# max1811smd.net
KiCad netlist of a schematic drawn in EAGLE
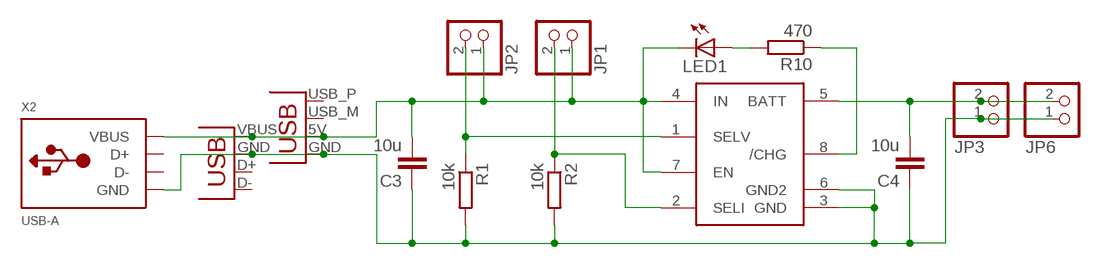
[diagram p0: schematic, sheet 1]

(export (version "E")
  (design (tool "Eeschema 10.0.6"))
  (components
    (comp (ref "C3")
      (value "10u")
      (footprint "eagle-import:C0805K")
      (libsource (lib "eagle-import") (part "C-EUC0805K"))
    )
    (comp (ref "C4")
      (value "10u")
      (footprint "eagle-import:C0805K")
      (libsource (lib "eagle-import") (part "C-EUC0805K"))
    )
    (comp (ref "CN1")
      (value "USBPCB")
      (footprint "eagle-import:USB-A-PCB")
      (libsource (lib "eagle-import") (part "USBPCB"))
    )
    (comp (ref "JP1")
      (value "PINHD-1X2")
      (footprint "eagle-import:1X02")
      (libsource (lib "eagle-import") (part "PINHD-1X2"))
    )
    (comp (ref "JP2")
      (value "PINHD-1X2")
      (footprint "eagle-import:1X02")
      (libsource (lib "eagle-import") (part "PINHD-1X2"))
    )
    (comp (ref "JP3")
      (value "PINHD-1X2")
      (footprint "eagle-import:1X02")
      (libsource (lib "eagle-import") (part "PINHD-1X2"))
    )
    (comp (ref "JP6")
      (value "PINHD-1X2")
      (footprint "eagle-import:1X02")
      (libsource (lib "eagle-import") (part "PINHD-1X2"))
    )
    (comp (ref "LED1")
      (value "LEDCHIPLED_0805")
      (footprint "eagle-import:CHIPLED_0805")
      (libsource (lib "eagle-import") (part "LEDCHIPLED_0805"))
    )
    (comp (ref "R1")
      (value "10k")
      (footprint "eagle-import:M0805")
      (libsource (lib "eagle-import") (part "R-EU_M0805"))
    )
    (comp (ref "R2")
      (value "10k")
      (footprint "eagle-import:M0805")
      (libsource (lib "eagle-import") (part "R-EU_M0805"))
    )
    (comp (ref "R10")
      (value "470")
      (footprint "eagle-import:M0805")
      (libsource (lib "eagle-import") (part "R-EU_M0805"))
    )
    (comp (ref "U$1")
      (value "MAX1811SO8")
      (footprint "eagle-import:SO08")
      (libsource (lib "eagle-import") (part "MAX1811SO8"))
    )
    (comp (ref "X1")
      (value "USB-A-H")
      (footprint "eagle-import:USB-A-H")
      (libsource (lib "eagle-import") (part "USB-A-H"))
    )
    (comp (ref "X2")
      (value "USB-A")
      (footprint "eagle-import:MOLEX_480371000")
      (libsource (lib "eagle-import") (part "USB-A"))
    )
  )
  (nets
    (net (code "1") (name "Net-(CN1-VBUS)") (class "Default")
      (node (ref "C3") (pin "2") (pinfunction "2_2") (pintype "passive"))
      (node (ref "CN1") (pin "5V") (pinfunction "VBUS_5V") (pintype "bidirectional"))
      (node (ref "JP1") (pin "1") (pinfunction "1_1") (pintype "passive"))
      (node (ref "JP2") (pin "1") (pinfunction "1_1") (pintype "passive"))
      (node (ref "LED1") (pin "C") (pinfunction "C_C") (pintype "passive"))
      (node (ref "U$1") (pin "4") (pinfunction "IN_4") (pintype "bidirectional"))
      (node (ref "U$1") (pin "7") (pinfunction "EN_7") (pintype "bidirectional"))
      (node (ref "X1") (pin "VBUS") (pinfunction "GND_VBUS") (pintype "bidirectional"))
      (node (ref "X2") (pin "1") (pinfunction "VBUS_1") (pintype "power_in"))
    )
    (net (code "2") (name "Net-(LED1-PadA)") (class "Default")
      (node (ref "LED1") (pin "A") (pinfunction "A_A") (pintype "passive"))
      (node (ref "R10") (pin "2") (pinfunction "2_2") (pintype "passive"))
    )
    (net (code "3") (name "Net-(U$1-BATT)") (class "Default")
      (node (ref "C4") (pin "2") (pinfunction "2_2") (pintype "passive"))
      (node (ref "JP3") (pin "2") (pinfunction "2_2") (pintype "passive"))
      (node (ref "JP6") (pin "2") (pinfunction "2_2") (pintype "passive"))
      (node (ref "U$1") (pin "5") (pinfunction "BATT_5") (pintype "bidirectional"))
    )
    (net (code "4") (name "Net-(U$1-GND)") (class "Default")
      (node (ref "C3") (pin "1") (pinfunction "1_1") (pintype "passive"))
      (node (ref "C4") (pin "1") (pinfunction "1_1") (pintype "passive"))
      (node (ref "CN1") (pin "GND") (pinfunction "GND_GND") (pintype "bidirectional"))
      (node (ref "JP3") (pin "1") (pinfunction "1_1") (pintype "passive"))
      (node (ref "JP6") (pin "1") (pinfunction "1_1") (pintype "passive"))
      (node (ref "R1") (pin "2") (pinfunction "2_2") (pintype "passive"))
      (node (ref "R2") (pin "2") (pinfunction "2_2") (pintype "passive"))
      (node (ref "U$1") (pin "3") (pinfunction "GND_3") (pintype "bidirectional"))
      (node (ref "U$1") (pin "6") (pinfunction "GND2_6") (pintype "bidirectional"))
      (node (ref "X1") (pin "GND") (pinfunction "VBUS_GND") (pintype "bidirectional"))
      (node (ref "X2") (pin "4") (pinfunction "GND_4") (pintype "power_in"))
    )
    (net (code "5") (name "Net-(U$1-SELI)") (class "Default")
      (node (ref "JP1") (pin "2") (pinfunction "2_2") (pintype "passive"))
      (node (ref "R2") (pin "1") (pinfunction "1_1") (pintype "passive"))
      (node (ref "U$1") (pin "2") (pinfunction "SELI_2") (pintype "bidirectional"))
    )
    (net (code "6") (name "Net-(U$1-SELV)") (class "Default")
      (node (ref "JP2") (pin "2") (pinfunction "2_2") (pintype "passive"))
      (node (ref "R1") (pin "1") (pinfunction "1_1") (pintype "passive"))
      (node (ref "U$1") (pin "1") (pinfunction "SELV_1") (pintype "bidirectional"))
    )
    (net (code "7") (name "Net-(U$1-{slash}CHG)") (class "Default")
      (node (ref "R10") (pin "1") (pinfunction "1_1") (pintype "passive"))
      (node (ref "U$1") (pin "8") (pinfunction "/CHG_8") (pintype "bidirectional"))
    )
    (net (code "8") (name "unconnected-(CN1-D+-PadUSB_P)") (class "Default")
      (node (ref "CN1") (pin "USB_P") (pinfunction "D+_USB_P") (pintype "bidirectional"))
    )
    (net (code "9") (name "unconnected-(CN1-D--PadUSB_M)") (class "Default")
      (node (ref "CN1") (pin "USB_M") (pinfunction "D-_USB_M") (pintype "bidirectional"))
    )
    (net (code "10") (name "unconnected-(X1-D+-PadD-)") (class "Default")
      (node (ref "X1") (pin "D-") (pinfunction "D+_D-") (pintype "bidirectional"))
    )
    (net (code "11") (name "unconnected-(X1-D--PadD+)") (class "Default")
      (node (ref "X1") (pin "D+") (pinfunction "D-_D+") (pintype "bidirectional"))
    )
    (net (code "12") (name "unconnected-(X2-D+-Pad3)") (class "Default")
      (node (ref "X2") (pin "3") (pinfunction "D+_3") (pintype "bidirectional"))
    )
    (net (code "13") (name "unconnected-(X2-D--Pad2)") (class "Default")
      (node (ref "X2") (pin "2") (pinfunction "D-_2") (pintype "bidirectional"))
    )
  )
)
